# bobby.net
KiCad netlist of a schematic drawn in EAGLE
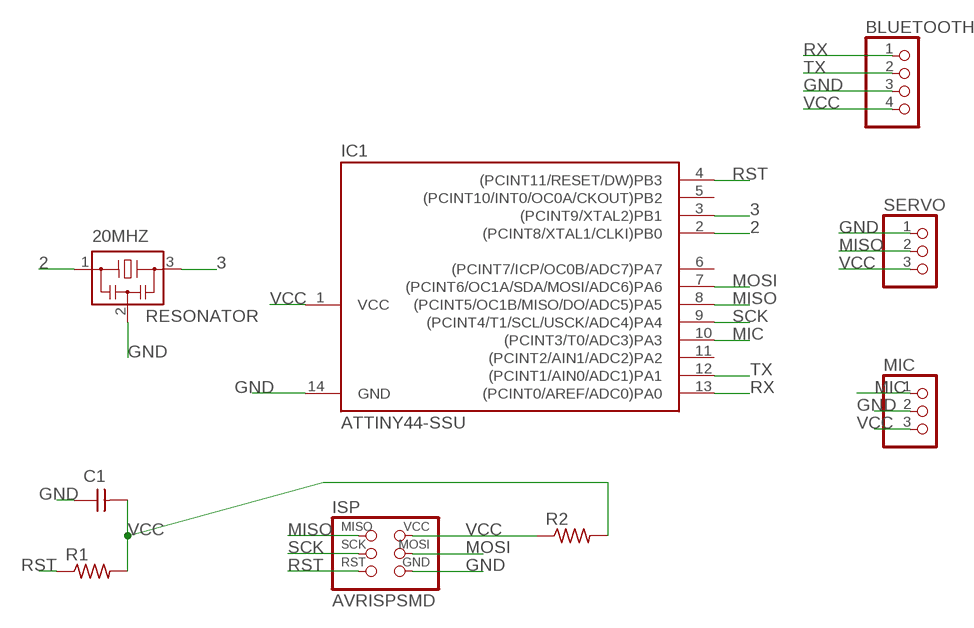
[diagram p0: schematic, sheet 1]

(export (version "E")
  (design (tool "Eeschema 10.0.6"))
  (components
    (comp (ref "20MHZ")
      (value "RESONATOR")
      (footprint "eagle-import:EFOBM")
      (libsource (lib "eagle-import") (part "RESONATOR"))
    )
    (comp (ref "BLUETOOTH")
      (value "PINHD-1X4/90")
      (footprint "eagle-import:1X04_90")
      (libsource (lib "eagle-import") (part "PINHD-1X4/90"))
    )
    (comp (ref "C1")
      (value "CAP-UNPOLARIZEDFAB")
      (footprint "eagle-import:C1206FAB")
      (libsource (lib "eagle-import") (part "CAP-UNPOLARIZEDFAB"))
    )
    (comp (ref "IC1")
      (value "ATTINY44-SSU")
      (footprint "eagle-import:SOIC14")
      (libsource (lib "eagle-import") (part "ATTINY44-SSU"))
    )
    (comp (ref "ISP")
      (value "AVRISPSMD")
      (footprint "eagle-import:2X03SMD")
      (libsource (lib "eagle-import") (part "AVRISPSMD"))
    )
    (comp (ref "MIC")
      (value "PINHD-1X3/90")
      (footprint "eagle-import:1X03_90")
      (libsource (lib "eagle-import") (part "PINHD-1X3/90"))
    )
    (comp (ref "R1")
      (value "RES-US1206FAB")
      (footprint "eagle-import:R1206FAB")
      (libsource (lib "eagle-import") (part "RES-US1206FAB"))
    )
    (comp (ref "R2")
      (value "RES-US1206FAB")
      (footprint "eagle-import:R1206FAB")
      (libsource (lib "eagle-import") (part "RES-US1206FAB"))
    )
    (comp (ref "SERVO")
      (value "PINHD-1X3/90")
      (footprint "eagle-import:1X03_90")
      (libsource (lib "eagle-import") (part "PINHD-1X3/90"))
    )
  )
  (nets
    (net (code "1") (name "/2") (class "Default")
      (node (ref "20MHZ") (pin "1") (pinfunction "1_1") (pintype "passive"))
      (node (ref "IC1") (pin "2") (pinfunction "(PCINT8/XTAL1/CLKI)PB0_2") (pintype "bidirectional"))
    )
    (net (code "2") (name "/3") (class "Default")
      (node (ref "20MHZ") (pin "3") (pinfunction "3_3") (pintype "passive"))
      (node (ref "IC1") (pin "3") (pinfunction "(PCINT9/XTAL2)PB1_3") (pintype "bidirectional"))
    )
    (net (code "3") (name "/GND") (class "Default")
      (node (ref "20MHZ") (pin "2") (pinfunction "2_2") (pintype "passive"))
      (node (ref "BLUETOOTH") (pin "3") (pinfunction "3_3") (pintype "passive"))
      (node (ref "C1") (pin "1") (pinfunction "1_1") (pintype "passive"))
      (node (ref "IC1") (pin "14") (pinfunction "GND_14") (pintype "power_in"))
      (node (ref "ISP") (pin "6") (pinfunction "GND_6") (pintype "passive"))
      (node (ref "MIC") (pin "2") (pinfunction "2_2") (pintype "passive"))
      (node (ref "SERVO") (pin "1") (pinfunction "1_1") (pintype "passive"))
    )
    (net (code "4") (name "/MIC") (class "Default")
      (node (ref "IC1") (pin "10") (pinfunction "(PCINT3/T0/ADC3)PA3_10") (pintype "bidirectional"))
      (node (ref "MIC") (pin "1") (pinfunction "1_1") (pintype "passive"))
    )
    (net (code "5") (name "/MISO") (class "Default")
      (node (ref "IC1") (pin "8") (pinfunction "(PCINT5/OC1B/MISO/DO/ADC5)PA5_8") (pintype "bidirectional"))
      (node (ref "ISP") (pin "1") (pinfunction "MISO_1") (pintype "passive"))
      (node (ref "SERVO") (pin "2") (pinfunction "2_2") (pintype "passive"))
    )
    (net (code "6") (name "/MOSI") (class "Default")
      (node (ref "IC1") (pin "7") (pinfunction "(PCINT6/OC1A/SDA/MOSI/ADC6)PA6_7") (pintype "bidirectional"))
      (node (ref "ISP") (pin "4") (pinfunction "MOSI_4") (pintype "passive"))
    )
    (net (code "7") (name "/RST") (class "Default")
      (node (ref "IC1") (pin "4") (pinfunction "(PCINT11/RESET/DW)PB3_4") (pintype "bidirectional"))
      (node (ref "ISP") (pin "5") (pinfunction "RST_5") (pintype "passive"))
      (node (ref "R1") (pin "1") (pinfunction "1_1") (pintype "passive"))
    )
    (net (code "8") (name "/RX") (class "Default")
      (node (ref "BLUETOOTH") (pin "1") (pinfunction "1_1") (pintype "passive"))
      (node (ref "IC1") (pin "13") (pinfunction "(PCINT0/AREF/ADC0)PA0_13") (pintype "bidirectional"))
    )
    (net (code "9") (name "/SCK") (class "Default")
      (node (ref "IC1") (pin "9") (pinfunction "(PCINT4/T1/SCL/USCK/ADC4)PA4_9") (pintype "bidirectional"))
      (node (ref "ISP") (pin "3") (pinfunction "SCK_3") (pintype "passive"))
    )
    (net (code "10") (name "/TX") (class "Default")
      (node (ref "BLUETOOTH") (pin "2") (pinfunction "2_2") (pintype "passive"))
      (node (ref "IC1") (pin "12") (pinfunction "(PCINT1/AIN0/ADC1)PA1_12") (pintype "bidirectional"))
    )
    (net (code "11") (name "/VCC") (class "Default")
      (node (ref "BLUETOOTH") (pin "4") (pinfunction "4_4") (pintype "passive"))
      (node (ref "C1") (pin "2") (pinfunction "2_2") (pintype "passive"))
      (node (ref "IC1") (pin "1") (pinfunction "VCC_1") (pintype "power_in"))
      (node (ref "ISP") (pin "2") (pinfunction "VCC_2") (pintype "passive"))
      (node (ref "MIC") (pin "3") (pinfunction "3_3") (pintype "passive"))
      (node (ref "R1") (pin "2") (pinfunction "2_2") (pintype "passive"))
      (node (ref "R2") (pin "1") (pinfunction "1_1") (pintype "passive"))
      (node (ref "R2") (pin "2") (pinfunction "2_2") (pintype "passive"))
      (node (ref "SERVO") (pin "3") (pinfunction "3_3") (pintype "passive"))
    )
    (net (code "12") (name "unconnected-(IC1-(PCINT2{slash}AIN1{slash}ADC2)PA2-Pad11)") (class "Default")
      (node (ref "IC1") (pin "11") (pinfunction "(PCINT2/AIN1/ADC2)PA2_11") (pintype "bidirectional"))
    )
    (net (code "13") (name "unconnected-(IC1-(PCINT7{slash}ICP{slash}OC0B{slash}ADC7)PA7-Pad6)") (class "Default")
      (node (ref "IC1") (pin "6") (pinfunction "(PCINT7/ICP/OC0B/ADC7)PA7_6") (pintype "bidirectional"))
    )
    (net (code "14") (name "unconnected-(IC1-(PCINT10{slash}INT0{slash}OC0A{slash}CKOUT)PB2-Pad5)") (class "Default")
      (node (ref "IC1") (pin "5") (pinfunction "(PCINT10/INT0/OC0A/CKOUT)PB2_5") (pintype "bidirectional"))
    )
  )
)
